# Ribbon_Connector_IO.net
KiCad netlist of a schematic drawn in Altium Designer
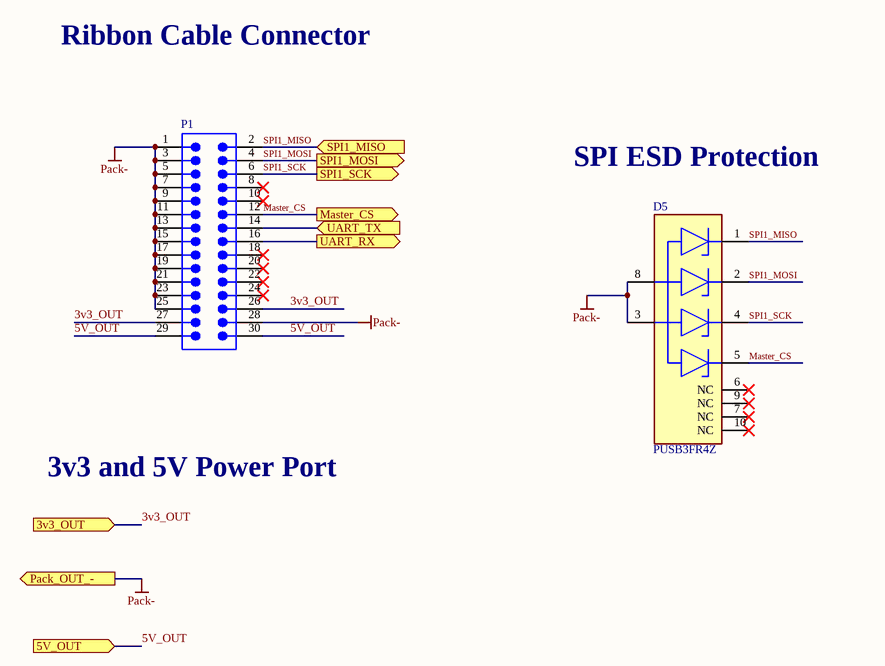
[diagram p0: Ribbon_Connector_IO.SchDoc]

(export (version "E")
  (design (tool "Eeschema 10.0.6"))
  (components
    (comp (ref "D5")
      (value "PUSB3FR4Z")
      (footprint "FP-SOT1176-1-MFG")
      (description "TVS DIODE 3.3VWM 3VC DFN2510A-10")
      (libsource (lib "Altium Content Vault") (part "7af82cefb99888626757485c32e8fb9"))
    )
    (comp (ref "P1")
      (value "62703021721")
      (footprint "62703021721")
      (description "62703021721 Conn, R/A Header, 30Pos, 2Row, 1.27Mm Rohs Compliant: Yes")
      (libsource (lib "Altium Content Vault") (part "Header_Male_2R_30P"))
    )
  )
  (nets
    (net (code "1") (name "/3v3_OUT") (class "Default")
      (node (ref "P1") (pin "26") (pinfunction "26_26") (pintype "passive"))
      (node (ref "P1") (pin "27") (pinfunction "27_27") (pintype "passive"))
    )
    (net (code "2") (name "/5V_OUT") (class "Default")
      (node (ref "P1") (pin "29") (pinfunction "29_29") (pintype "passive"))
      (node (ref "P1") (pin "30") (pinfunction "30_30") (pintype "passive"))
    )
    (net (code "3") (name "/Master_CS") (class "Default")
      (node (ref "D5") (pin "5") (pinfunction "CH4_5") (pintype "passive"))
      (node (ref "P1") (pin "12") (pinfunction "12_12") (pintype "passive"))
    )
    (net (code "4") (name "/SPI1_MISO") (class "Default")
      (node (ref "D5") (pin "1") (pinfunction "CH1_1") (pintype "passive"))
      (node (ref "P1") (pin "2") (pinfunction "2_2") (pintype "passive"))
    )
    (net (code "5") (name "/SPI1_MOSI") (class "Default")
      (node (ref "D5") (pin "2") (pinfunction "CH2_2") (pintype "passive"))
      (node (ref "P1") (pin "4") (pinfunction "4_4") (pintype "passive"))
    )
    (net (code "6") (name "/SPI1_SCK") (class "Default")
      (node (ref "D5") (pin "4") (pinfunction "CH3_4") (pintype "passive"))
      (node (ref "P1") (pin "6") (pinfunction "6_6") (pintype "passive"))
    )
    (net (code "7") (name "/UART_RX") (class "Default")
      (node (ref "P1") (pin "16") (pinfunction "16_16") (pintype "passive"))
    )
    (net (code "8") (name "/UART_TX") (class "Default")
      (node (ref "P1") (pin "14") (pinfunction "14_14") (pintype "passive"))
    )
    (net (code "9") (name "Pack-") (class "Default")
      (node (ref "D5") (pin "3") (pinfunction "GND_3") (pintype "power_in"))
      (node (ref "D5") (pin "8") (pinfunction "GND_8") (pintype "power_in"))
      (node (ref "P1") (pin "1") (pinfunction "1_1") (pintype "passive"))
      (node (ref "P1") (pin "11") (pinfunction "11_11") (pintype "passive"))
      (node (ref "P1") (pin "13") (pinfunction "13_13") (pintype "passive"))
      (node (ref "P1") (pin "15") (pinfunction "15_15") (pintype "passive"))
      (node (ref "P1") (pin "17") (pinfunction "17_17") (pintype "passive"))
      (node (ref "P1") (pin "19") (pinfunction "19_19") (pintype "passive"))
      (node (ref "P1") (pin "21") (pinfunction "21_21") (pintype "passive"))
      (node (ref "P1") (pin "23") (pinfunction "23_23") (pintype "passive"))
      (node (ref "P1") (pin "25") (pinfunction "25_25") (pintype "passive"))
      (node (ref "P1") (pin "28") (pinfunction "28_28") (pintype "passive"))
      (node (ref "P1") (pin "3") (pinfunction "3_3") (pintype "passive"))
      (node (ref "P1") (pin "5") (pinfunction "5_5") (pintype "passive"))
      (node (ref "P1") (pin "7") (pinfunction "7_7") (pintype "passive"))
      (node (ref "P1") (pin "9") (pinfunction "9_9") (pintype "passive"))
    )
    (net (code "10") (name "unconnected-(D5-NC-Pad6)") (class "Default")
      (node (ref "D5") (pin "6") (pinfunction "NC_6") (pintype "passive+no_connect"))
    )
    (net (code "11") (name "unconnected-(D5-NC-Pad7)") (class "Default")
      (node (ref "D5") (pin "7") (pinfunction "NC_7") (pintype "passive+no_connect"))
    )
    (net (code "12") (name "unconnected-(D5-NC-Pad9)") (class "Default")
      (node (ref "D5") (pin "9") (pinfunction "NC_9") (pintype "passive+no_connect"))
    )
    (net (code "13") (name "unconnected-(D5-NC-Pad10)") (class "Default")
      (node (ref "D5") (pin "10") (pinfunction "NC_10") (pintype "passive+no_connect"))
    )
    (net (code "14") (name "unconnected-(P1-Pad8)") (class "Default")
      (node (ref "P1") (pin "8") (pinfunction "8_8") (pintype "passive+no_connect"))
    )
    (net (code "15") (name "unconnected-(P1-Pad10)") (class "Default")
      (node (ref "P1") (pin "10") (pinfunction "10_10") (pintype "passive+no_connect"))
    )
    (net (code "16") (name "unconnected-(P1-Pad18)") (class "Default")
      (node (ref "P1") (pin "18") (pinfunction "18_18") (pintype "passive+no_connect"))
    )
    (net (code "17") (name "unconnected-(P1-Pad20)") (class "Default")
      (node (ref "P1") (pin "20") (pinfunction "20_20") (pintype "passive+no_connect"))
    )
    (net (code "18") (name "unconnected-(P1-Pad22)") (class "Default")
      (node (ref "P1") (pin "22") (pinfunction "22_22") (pintype "passive+no_connect"))
    )
    (net (code "19") (name "unconnected-(P1-Pad24)") (class "Default")
      (node (ref "P1") (pin "24") (pinfunction "24_24") (pintype "passive+no_connect"))
    )
  )
)
